# Power.net
KiCad netlist of a schematic drawn in Altium Designer
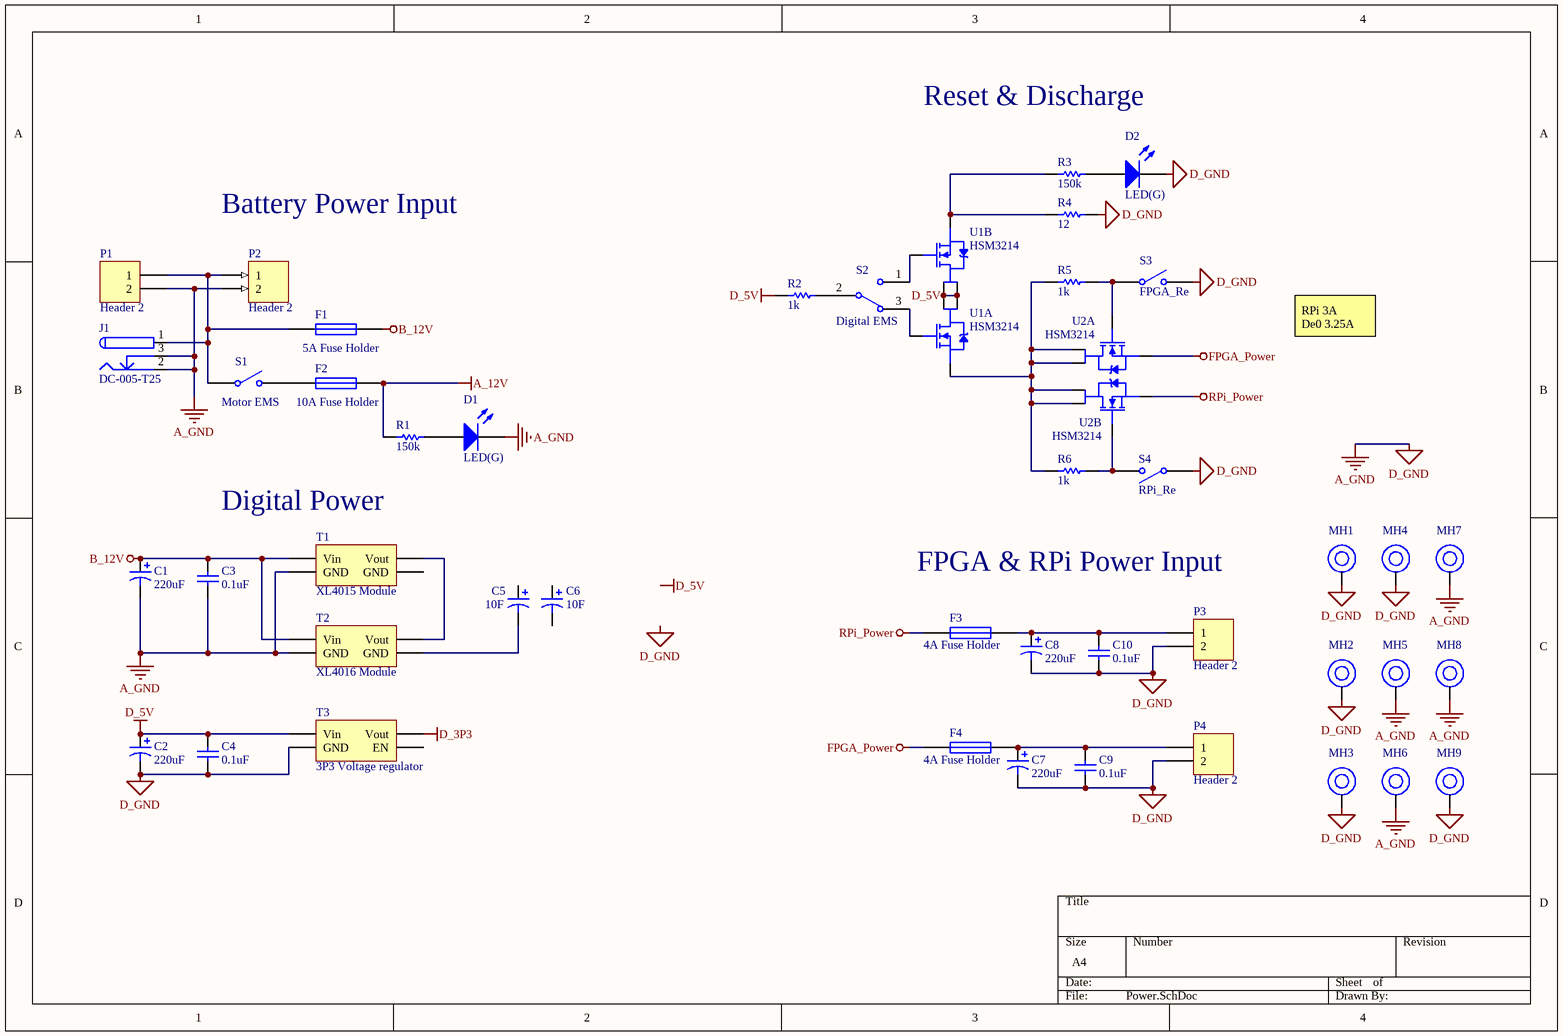
[diagram p0: Power.SchDoc]

(export (version "E")
  (design (tool "Eeschema 10.0.6"))
  (components
    (comp (ref "C1")
      (value "220uF")
      (footprint "OWMR:VZT221M1ETR-0607")
      (fields (field (name "PUBLISHER") "Altium Limited"))
      (libsource (lib "Miscellaneous Devices") (part "Cap Pol1"))
    )
    (comp (ref "C2")
      (value "220uF")
      (footprint "OWMR:VZT221M1ETR-0607")
      (fields (field (name "PUBLISHER") "Altium Limited"))
      (libsource (lib "Miscellaneous Devices") (part "Cap Pol1"))
    )
    (comp (ref "C3")
      (value "0.1uF")
      (footprint "OWMR:1210B104K500NT")
      (description "50V 100nF X7R ±10% 1210  Multilayer Ceramic Capacitors MLCC - SMD/SMT ROHS")
      (fields (field (name "PUBLISHER") "Altium Limited"))
      (libsource (lib "Miscellaneous Devices") (part "Cap Semi"))
    )
    (comp (ref "C4")
      (value "0.1uF")
      (footprint "OWMR:1210B104K500NT")
      (description "50V 100nF X7R ±10% 1210  Multilayer Ceramic Capacitors MLCC - SMD/SMT ROHS")
      (fields (field (name "PUBLISHER") "Altium Limited"))
      (libsource (lib "Miscellaneous Devices") (part "Cap Semi"))
    )
    (comp (ref "C5")
      (value "10F")
      (footprint "OWMR:SUPPYCAP-DIP_L33.0_W16.5")
      (description "CAPACITOR 10F -10% +30% 5.5V T/H")
      (fields (field (name "PUBLISHER") "Altium Limited"))
      (libsource (lib "Miscellaneous Devices") (part "Cap Pol1"))
    )
    (comp (ref "C6")
      (value "10F")
      (footprint "OWMR:SUPPYCAP-DIP_L33.0_W16.5")
      (description "CAPACITOR 10F -10% +30% 5.5V T/H")
      (fields (field (name "PUBLISHER") "Altium Limited"))
      (libsource (lib "Miscellaneous Devices") (part "Cap Pol1"))
    )
    (comp (ref "C7")
      (value "220uF")
      (footprint "OWMR:VZT221M1ETR-0607")
      (fields (field (name "PUBLISHER") "Altium Limited"))
      (libsource (lib "Miscellaneous Devices") (part "Cap Pol1"))
    )
    (comp (ref "C8")
      (value "220uF")
      (footprint "OWMR:VZT221M1ETR-0607")
      (fields (field (name "PUBLISHER") "Altium Limited"))
      (libsource (lib "Miscellaneous Devices") (part "Cap Pol1"))
    )
    (comp (ref "C9")
      (value "0.1uF")
      (footprint "OWMR:1210B104K500NT")
      (description "50V 100nF X7R ±10% 1210  Multilayer Ceramic Capacitors MLCC - SMD/SMT ROHS")
      (fields (field (name "PUBLISHER") "Altium Limited"))
      (libsource (lib "Miscellaneous Devices") (part "Cap Semi"))
    )
    (comp (ref "C10")
      (value "0.1uF")
      (footprint "OWMR:1210B104K500NT")
      (description "50V 100nF X7R ±10% 1210  Multilayer Ceramic Capacitors MLCC - SMD/SMT ROHS")
      (fields (field (name "PUBLISHER") "Altium Limited"))
      (libsource (lib "Miscellaneous Devices") (part "Cap Semi"))
    )
    (comp (ref "D1")
      (value "LED(G)")
      (footprint "OWMR:BL-HG036D-AV-TRB")
      (description "Green-yellow 0603 Light Emitting Diodes (LED) RoHS")
      (fields (field (name "PUBLISHER") "Altium Limited"))
      (libsource (lib "Miscellaneous Devices") (part "LED0"))
    )
    (comp (ref "D2")
      (value "LED(G)")
      (footprint "OWMR:BL-HG036D-AV-TRB")
      (description "Green-yellow 0603 Light Emitting Diodes (LED) RoHS")
      (fields (field (name "PUBLISHER") "Altium Limited"))
      (libsource (lib "Miscellaneous Devices") (part "LED0"))
    )
    (comp (ref "F1")
      (value "5A Fuse Holder")
      (footprint "OWMR:SMD Fuses Holder")
      (fields (field (name "PUBLISHER") "Altium Limited"))
      (libsource (lib "Miscellaneous Devices") (part "Fuse 1"))
    )
    (comp (ref "F2")
      (value "10A Fuse Holder")
      (footprint "OWMR:SMD Fuses Holder")
      (fields (field (name "PUBLISHER") "Altium Limited"))
      (libsource (lib "Miscellaneous Devices") (part "Fuse 1"))
    )
    (comp (ref "F3")
      (value "4A Fuse Holder")
      (footprint "OWMR:SMD Fuses Holder")
      (fields (field (name "PUBLISHER") "Altium Limited"))
      (libsource (lib "Miscellaneous Devices") (part "Fuse 1"))
    )
    (comp (ref "F4")
      (value "4A Fuse Holder")
      (footprint "OWMR:SMD Fuses Holder")
      (fields (field (name "PUBLISHER") "Altium Limited"))
      (libsource (lib "Miscellaneous Devices") (part "Fuse 1"))
    )
    (comp (ref "J1")
      (value "DC-005-T25")
      (footprint "OWMR:DC-005-T25")
      (description "Shrouded DC Power Receptacle -10℃~+60℃ 2.5mm 6.3mm 3A 30V Plugin AC/DC Power Connectors ROHS")
      (fields (field (name "PUBLISHER") "Altium Limited"))
      (libsource (lib "Miscellaneous Connectors") (part "PWR2.5"))
    )
    (comp (ref "MH1") (value "M3 Hole") (footprint "OWMR:M3 Hole") (libsource (lib "OWMR") (part "M3_Hole")))
    (comp (ref "MH2") (value "M3 Hole") (footprint "OWMR:M3 Hole") (libsource (lib "OWMR") (part "M3_Hole")))
    (comp (ref "MH3") (value "M3 Hole") (footprint "OWMR:M3 Hole") (libsource (lib "OWMR") (part "M3_Hole")))
    (comp (ref "MH4") (value "M3 Hole") (footprint "OWMR:M3 Hole") (libsource (lib "OWMR") (part "M3_Hole")))
    (comp (ref "MH5") (value "M3 Hole") (footprint "OWMR:M3 Hole") (libsource (lib "OWMR") (part "M3_Hole")))
    (comp (ref "MH6") (value "M3 Hole") (footprint "OWMR:M3 Hole") (libsource (lib "OWMR") (part "M3_Hole")))
    (comp (ref "MH7") (value "M3 Hole") (footprint "OWMR:M3 Hole") (libsource (lib "OWMR") (part "M3_Hole")))
    (comp (ref "MH8") (value "M3 Hole") (footprint "OWMR:M3 Hole") (libsource (lib "OWMR") (part "M3_Hole")))
    (comp (ref "MH9") (value "M3 Hole") (footprint "OWMR:M3 Hole") (libsource (lib "OWMR") (part "M3_Hole")))
    (comp (ref "P1")
      (value "Header 2")
      (footprint "OWMR:XT60PW-M")
      (description "XT60PW-F 500V 45A Through Hole Power Connectors ROHS")
      (fields (field (name "PUBLISHER") "Altium Limited"))
      (libsource (lib "") (part "Header 2_2"))
    )
    (comp (ref "P2")
      (value "Header 2")
      (footprint "OWMR:B2B-XH-A(LF)(SN)")
      (description "1x2P XH 1 2.5mm 2 Brass Plugin,P=2.5mm  Wire To Board / Wire To Wire Connector ROHS")
      (fields (field (name "PUBLISHER") "Altium Limited"))
      (libsource (lib "Miscellaneous Connectors") (part "Header 2"))
    )
    (comp (ref "P3")
      (value "Header 2")
      (footprint "OWMR:B2B-XH-A(LF)(SN)")
      (description "1x2P XH 1 2.5mm 2 Brass Plugin,P=2.5mm  Wire To Board / Wire To Wire Connector ROHS")
      (fields (field (name "PUBLISHER") "Altium Limited"))
      (libsource (lib "") (part "Header 2_1"))
    )
    (comp (ref "P4")
      (value "Header 2")
      (footprint "OWMR:B2B-XH-A(LF)(SN)")
      (description "1x2P XH 1 2.5mm 2 Brass Plugin,P=2.5mm  Wire To Board / Wire To Wire Connector ROHS")
      (fields (field (name "PUBLISHER") "Altium Limited"))
      (libsource (lib "") (part "Header 2_1"))
    )
    (comp (ref "R1")
      (value "150k")
      (footprint "OWMR:RS-03K1503FT")
      (description "100mW 50V ±1% ±100ppm/℃ -55℃~+155℃ 150kΩ 0603  Chip Resistor - Surface Mount ROHS")
      (fields (field (name "PUBLISHER") "Altium Limited"))
      (libsource (lib "Miscellaneous Devices") (part "Res1"))
    )
    (comp (ref "R2")
      (value "1k")
      (footprint "OWMR:RS-03K1503FT")
      (description "100mW 50V ±1% ±100ppm/℃ -55℃~+155℃ 150kΩ 0603  Chip Resistor - Surface Mount ROHS")
      (fields (field (name "PUBLISHER") "Altium Limited"))
      (libsource (lib "Miscellaneous Devices") (part "Res1"))
    )
    (comp (ref "R3")
      (value "150k")
      (footprint "OWMR:RS-03K1503FT")
      (description "100mW 50V ±1% ±100ppm/℃ -55℃~+155℃ 150kΩ 0603  Chip Resistor - Surface Mount ROHS")
      (fields (field (name "PUBLISHER") "Altium Limited"))
      (libsource (lib "Miscellaneous Devices") (part "Res1"))
    )
    (comp (ref "R4")
      (value "12")
      (footprint "OWMR:MOF3WS-12Ω±5%T")
      (description "Metal Oxide Resistors 12Ω 3W ±700ppm/℃ ±5% Axial Leaded  Through Hole Resistors ROHS")
      (fields (field (name "PUBLISHER") "Altium Limited"))
      (libsource (lib "Miscellaneous Devices") (part "Res1"))
    )
    (comp (ref "R5")
      (value "1k")
      (footprint "OWMR:RS-03K1503FT")
      (description "100mW 50V ±1% ±100ppm/℃ -55℃~+155℃ 150kΩ 0603  Chip Resistor - Surface Mount ROHS")
      (fields (field (name "PUBLISHER") "Altium Limited"))
      (libsource (lib "Miscellaneous Devices") (part "Res1"))
    )
    (comp (ref "R6")
      (value "1k")
      (footprint "OWMR:RS-03K1503FT")
      (description "100mW 50V ±1% ±100ppm/℃ -55℃~+155℃ 150kΩ 0603  Chip Resistor - Surface Mount ROHS")
      (fields (field (name "PUBLISHER") "Altium Limited"))
      (libsource (lib "Miscellaneous Devices") (part "Res1"))
    )
    (comp (ref "S1")
      (value "Motor EMS")
      (footprint "OWMR:JNQ032")
      (fields (field (name "PUBLISHER") "Altium Limited"))
      (libsource (lib "Miscellaneous Devices") (part "SW-SPST"))
    )
    (comp (ref "S2")
      (value "Digital EMS")
      (footprint "OWMR:ST-0-102-C03-N003-RS")
      (description "Cylindrical button handle 125V -25℃~85℃ SPDT PCPin 40000 3A Plugin  Toggle Switches ROHS")
      (fields (field (name "PUBLISHER") "Altium Limited"))
      (libsource (lib "Miscellaneous Devices") (part "SW-SPDT"))
    )
    (comp (ref "S3")
      (value "FPGA_Re")
      (footprint "OWMR:SKHMQLE010")
      (description "6.2mm 3.1mm Round Button 50mA Brick nogging 6.5mm SPST 12V SMD  Tactile Switches ROHS")
      (fields (field (name "PUBLISHER") "Altium Limited"))
      (libsource (lib "Miscellaneous Devices") (part "SW-SPST"))
    )
    (comp (ref "S4")
      (value "RPi_Re")
      (footprint "OWMR:SKHMQKE010")
      (description "6.2mm 3.1mm Round Button 50mA Brick nogging 6.5mm SPST 12V SMD  Tactile Switches ROHS")
      (fields (field (name "PUBLISHER") "Altium Limited"))
      (libsource (lib "Miscellaneous Devices") (part "SW-SPST"))
    )
    (comp (ref "T1")
      (value "XL4015 Module")
      (footprint "OWMR:XL4015 Voltage Regulator Module")
      (libsource (lib "") (part "Non-isolated Voltage regulator_1"))
    )
    (comp (ref "T2")
      (value "XL4016 Module")
      (footprint "OWMR:XH-M401 Voltage Regulator Module")
      (description "NO Step-down type 1 Step-down 1.25V~36V 8V~40V 8A 180kHz TO-220-5  DC-DC Converters ROHS")
      (libsource (lib "") (part "Non-isolated Voltage regulator_1"))
    )
    (comp (ref "T3")
      (value "3P3 Voltage regulator")
      (footprint "OWMR:Small Voltage regulator module")
      (description "3A Non-isolated Voltage Regulator")
      (libsource (lib "OWMR") (part "Non-isolated Voltage regulator"))
    )
    (comp (ref "U1")
      (value "HSM3214")
      (footprint "OWMR:HSM3214")
      (description "30V 10A 12mΩ@10V,8A 1.5W 2.5V@250μA 2 N-Channel SOP-8  MOSFETs ROHS")
      (libsource (lib "OWMR") (part "HSM3214"))
    )
    (comp (ref "U2")
      (value "HSM3214")
      (footprint "OWMR:HSM3214")
      (description "30V 10A 12mΩ@10V,8A 1.5W 2.5V@250μA 2 N-Channel SOP-8  MOSFETs ROHS")
      (libsource (lib "OWMR") (part "HSM3214"))
    )
  )
  (nets
    (net (code "1") (name "A_12V") (class "Default")
      (node (ref "F2") (pin "2") (pinfunction "2_2") (pintype "passive"))
      (node (ref "R1") (pin "2") (pinfunction "2_2") (pintype "passive"))
    )
    (net (code "2") (name "A_GND") (class "Default")
      (node (ref "C1") (pin "2") (pinfunction "2_2") (pintype "passive"))
      (node (ref "C10") (pin "1") (pinfunction "1_1") (pintype "passive"))
      (node (ref "C2") (pin "2") (pinfunction "2_2") (pintype "passive"))
      (node (ref "C3") (pin "1") (pinfunction "1_1") (pintype "passive"))
      (node (ref "C4") (pin "1") (pinfunction "1_1") (pintype "passive"))
      (node (ref "C7") (pin "2") (pinfunction "2_2") (pintype "passive"))
      (node (ref "C8") (pin "2") (pinfunction "2_2") (pintype "passive"))
      (node (ref "C9") (pin "1") (pinfunction "1_1") (pintype "passive"))
      (node (ref "D1") (pin "2") (pinfunction "K_2") (pintype "passive"))
      (node (ref "D2") (pin "2") (pinfunction "K_2") (pintype "passive"))
      (node (ref "J1") (pin "2") (pinfunction "2_2") (pintype "power_in"))
      (node (ref "J1") (pin "3") (pinfunction "3_3") (pintype "power_in"))
      (node (ref "MH1") (pin "1") (pintype "passive"))
      (node (ref "MH2") (pin "1") (pintype "passive"))
      (node (ref "MH3") (pin "1") (pintype "passive"))
      (node (ref "MH4") (pin "1") (pintype "passive"))
      (node (ref "MH5") (pin "1") (pintype "passive"))
      (node (ref "MH6") (pin "1") (pintype "passive"))
      (node (ref "MH7") (pin "1") (pintype "passive"))
      (node (ref "MH8") (pin "1") (pintype "passive"))
      (node (ref "MH9") (pin "1") (pintype "passive"))
      (node (ref "P1") (pin "2") (pinfunction "2_2") (pintype "power_in"))
      (node (ref "P2") (pin "2") (pinfunction "2_2") (pintype "input"))
      (node (ref "P3") (pin "2") (pinfunction "2_2") (pintype "passive"))
      (node (ref "P4") (pin "2") (pinfunction "2_2") (pintype "passive"))
      (node (ref "R4") (pin "1") (pinfunction "1_1") (pintype "passive"))
      (node (ref "S3") (pin "2") (pinfunction "NO_2") (pintype "passive"))
      (node (ref "S4") (pin "1") (pinfunction "COMMON_1") (pintype "passive"))
      (node (ref "T1") (pin "2") (pinfunction "GND_2") (pintype "power_in"))
      (node (ref "T2") (pin "2") (pinfunction "GND_2") (pintype "power_in"))
      (node (ref "T3") (pin "2") (pinfunction "GND_2") (pintype "power_in"))
    )
    (net (code "3") (name "B_12V") (class "Default")
      (node (ref "C1") (pin "1") (pinfunction "1_1") (pintype "passive"))
      (node (ref "C3") (pin "2") (pinfunction "2_2") (pintype "passive"))
      (node (ref "F1") (pin "2") (pinfunction "2_2") (pintype "passive"))
      (node (ref "T1") (pin "1") (pinfunction "Vin_1") (pintype "power_in"))
      (node (ref "T2") (pin "1") (pinfunction "Vin_1") (pintype "power_in"))
    )
    (net (code "4") (name "D_3P3") (class "Default")
      (node (ref "T3") (pin "3") (pinfunction "Vout_3") (pintype "power_in"))
    )
    (net (code "5") (name "D_5V") (class "Default")
      (node (ref "C2") (pin "1") (pinfunction "1_1") (pintype "passive"))
      (node (ref "C4") (pin "2") (pinfunction "2_2") (pintype "passive"))
      (node (ref "R2") (pin "2") (pinfunction "2_2") (pintype "passive"))
      (node (ref "T3") (pin "1") (pinfunction "Vin_1") (pintype "power_in"))
      (node (ref "U1") (pin "5") (pinfunction "D1_5") (pintype "passive"))
      (node (ref "U1") (pin "6") (pinfunction "D1_6") (pintype "passive"))
      (node (ref "U1") (pin "7") (pinfunction "D1_7") (pintype "passive"))
      (node (ref "U1") (pin "8") (pinfunction "D1_8") (pintype "passive"))
    )
    (net (code "6") (name "FPGA_Power") (class "Default")
      (node (ref "F4") (pin "1") (pinfunction "1_1") (pintype "passive"))
      (node (ref "U2") (pin "1") (pinfunction "S1_1") (pintype "passive"))
    )
    (net (code "7") (name "Net-(C5-Pad2)") (class "Default")
      (node (ref "C5") (pin "2") (pinfunction "2_2") (pintype "passive"))
      (node (ref "T2") (pin "4") (pinfunction "GND_4") (pintype "power_in"))
    )
    (net (code "8") (name "Net-(C7-Pad1)") (class "Default")
      (node (ref "C7") (pin "1") (pinfunction "1_1") (pintype "passive"))
      (node (ref "C9") (pin "2") (pinfunction "2_2") (pintype "passive"))
      (node (ref "F4") (pin "2") (pinfunction "2_2") (pintype "passive"))
      (node (ref "P4") (pin "1") (pinfunction "1_1") (pintype "passive"))
    )
    (net (code "9") (name "Net-(C10-Pad2)") (class "Default")
      (node (ref "C10") (pin "2") (pinfunction "2_2") (pintype "passive"))
      (node (ref "C8") (pin "1") (pinfunction "1_1") (pintype "passive"))
      (node (ref "F3") (pin "2") (pinfunction "2_2") (pintype "passive"))
      (node (ref "P3") (pin "1") (pinfunction "1_1") (pintype "passive"))
    )
    (net (code "10") (name "Net-(D1-A)") (class "Default")
      (node (ref "D1") (pin "1") (pinfunction "A_1") (pintype "passive"))
      (node (ref "R1") (pin "1") (pinfunction "1_1") (pintype "passive"))
    )
    (net (code "11") (name "Net-(D2-A)") (class "Default")
      (node (ref "D2") (pin "1") (pinfunction "A_1") (pintype "passive"))
      (node (ref "R3") (pin "1") (pinfunction "1_1") (pintype "passive"))
    )
    (net (code "12") (name "Net-(R2-Pad1)") (class "Default")
      (node (ref "R2") (pin "1") (pinfunction "1_1") (pintype "passive"))
      (node (ref "S2") (pin "2") (pinfunction "2_2") (pintype "passive"))
    )
    (net (code "13") (name "Net-(S1-COMMON)") (class "Default")
      (node (ref "F1") (pin "1") (pinfunction "1_1") (pintype "passive"))
      (node (ref "J1") (pin "1") (pinfunction "1_1") (pintype "power_in"))
      (node (ref "P1") (pin "1") (pinfunction "1_1") (pintype "power_in"))
      (node (ref "P2") (pin "1") (pinfunction "1_1") (pintype "input"))
      (node (ref "S1") (pin "1") (pinfunction "COMMON_1") (pintype "passive"))
    )
    (net (code "14") (name "Net-(S1-NO)") (class "Default")
      (node (ref "F2") (pin "1") (pinfunction "1_1") (pintype "passive"))
      (node (ref "S1") (pin "2") (pinfunction "NO_2") (pintype "passive"))
    )
    (net (code "15") (name "Net-(S3-COMMON)") (class "Default")
      (node (ref "R5") (pin "1") (pinfunction "1_1") (pintype "passive"))
      (node (ref "S3") (pin "1") (pinfunction "COMMON_1") (pintype "passive"))
      (node (ref "U2") (pin "2") (pinfunction "G1_2") (pintype "passive"))
    )
    (net (code "16") (name "Net-(S4-NO)") (class "Default")
      (node (ref "R6") (pin "1") (pinfunction "1_1") (pintype "passive"))
      (node (ref "S4") (pin "2") (pinfunction "NO_2") (pintype "passive"))
      (node (ref "U2") (pin "4") (pinfunction "G1_4") (pintype "passive"))
    )
    (net (code "17") (name "Net-(T1-Vout)") (class "Default")
      (node (ref "T1") (pin "3") (pinfunction "Vout_3") (pintype "power_in"))
      (node (ref "T2") (pin "3") (pinfunction "Vout_3") (pintype "power_in"))
    )
    (net (code "18") (name "Net-(U1A-G1)") (class "Default")
      (node (ref "S2") (pin "3") (pinfunction "3_3") (pintype "passive"))
      (node (ref "U1") (pin "2") (pinfunction "G1_2") (pintype "passive"))
    )
    (net (code "19") (name "Net-(U1A-S1)") (class "Default")
      (node (ref "R5") (pin "2") (pinfunction "2_2") (pintype "passive"))
      (node (ref "R6") (pin "2") (pinfunction "2_2") (pintype "passive"))
      (node (ref "U1") (pin "1") (pinfunction "S1_1") (pintype "passive"))
      (node (ref "U2") (pin "5") (pinfunction "D1_5") (pintype "passive"))
      (node (ref "U2") (pin "6") (pinfunction "D1_6") (pintype "passive"))
      (node (ref "U2") (pin "7") (pinfunction "D1_7") (pintype "passive"))
      (node (ref "U2") (pin "8") (pinfunction "D1_8") (pintype "passive"))
    )
    (net (code "20") (name "Net-(U1B-G1)") (class "Default")
      (node (ref "S2") (pin "1") (pinfunction "1_1") (pintype "passive"))
      (node (ref "U1") (pin "4") (pinfunction "G1_4") (pintype "passive"))
    )
    (net (code "21") (name "Net-(U1B-S1)") (class "Default")
      (node (ref "R3") (pin "2") (pinfunction "2_2") (pintype "passive"))
      (node (ref "R4") (pin "2") (pinfunction "2_2") (pintype "passive"))
      (node (ref "U1") (pin "3") (pinfunction "S1_3") (pintype "passive"))
    )
    (net (code "22") (name "RPi_Power") (class "Default")
      (node (ref "F3") (pin "1") (pinfunction "1_1") (pintype "passive"))
      (node (ref "U2") (pin "3") (pinfunction "S1_3") (pintype "passive"))
    )
    (net (code "23") (name "unconnected-(C5-Pad1)") (class "Default")
      (node (ref "C5") (pin "1") (pinfunction "1_1") (pintype "passive"))
    )
    (net (code "24") (name "unconnected-(C6-Pad1)") (class "Default")
      (node (ref "C6") (pin "1") (pinfunction "1_1") (pintype "passive"))
    )
    (net (code "25") (name "unconnected-(C6-Pad2)") (class "Default")
      (node (ref "C6") (pin "2") (pinfunction "2_2") (pintype "passive"))
    )
    (net (code "26") (name "unconnected-(T1-GND-Pad4)") (class "Default")
      (node (ref "T1") (pin "4") (pinfunction "GND_4") (pintype "power_in"))
    )
    (net (code "27") (name "unconnected-(T3-EN-Pad4)") (class "Default")
      (node (ref "T3") (pin "4") (pinfunction "EN_4") (pintype "power_in"))
    )
  )
)
